# 03_I2S.net
KiCad netlist of a schematic drawn in Altium Designer
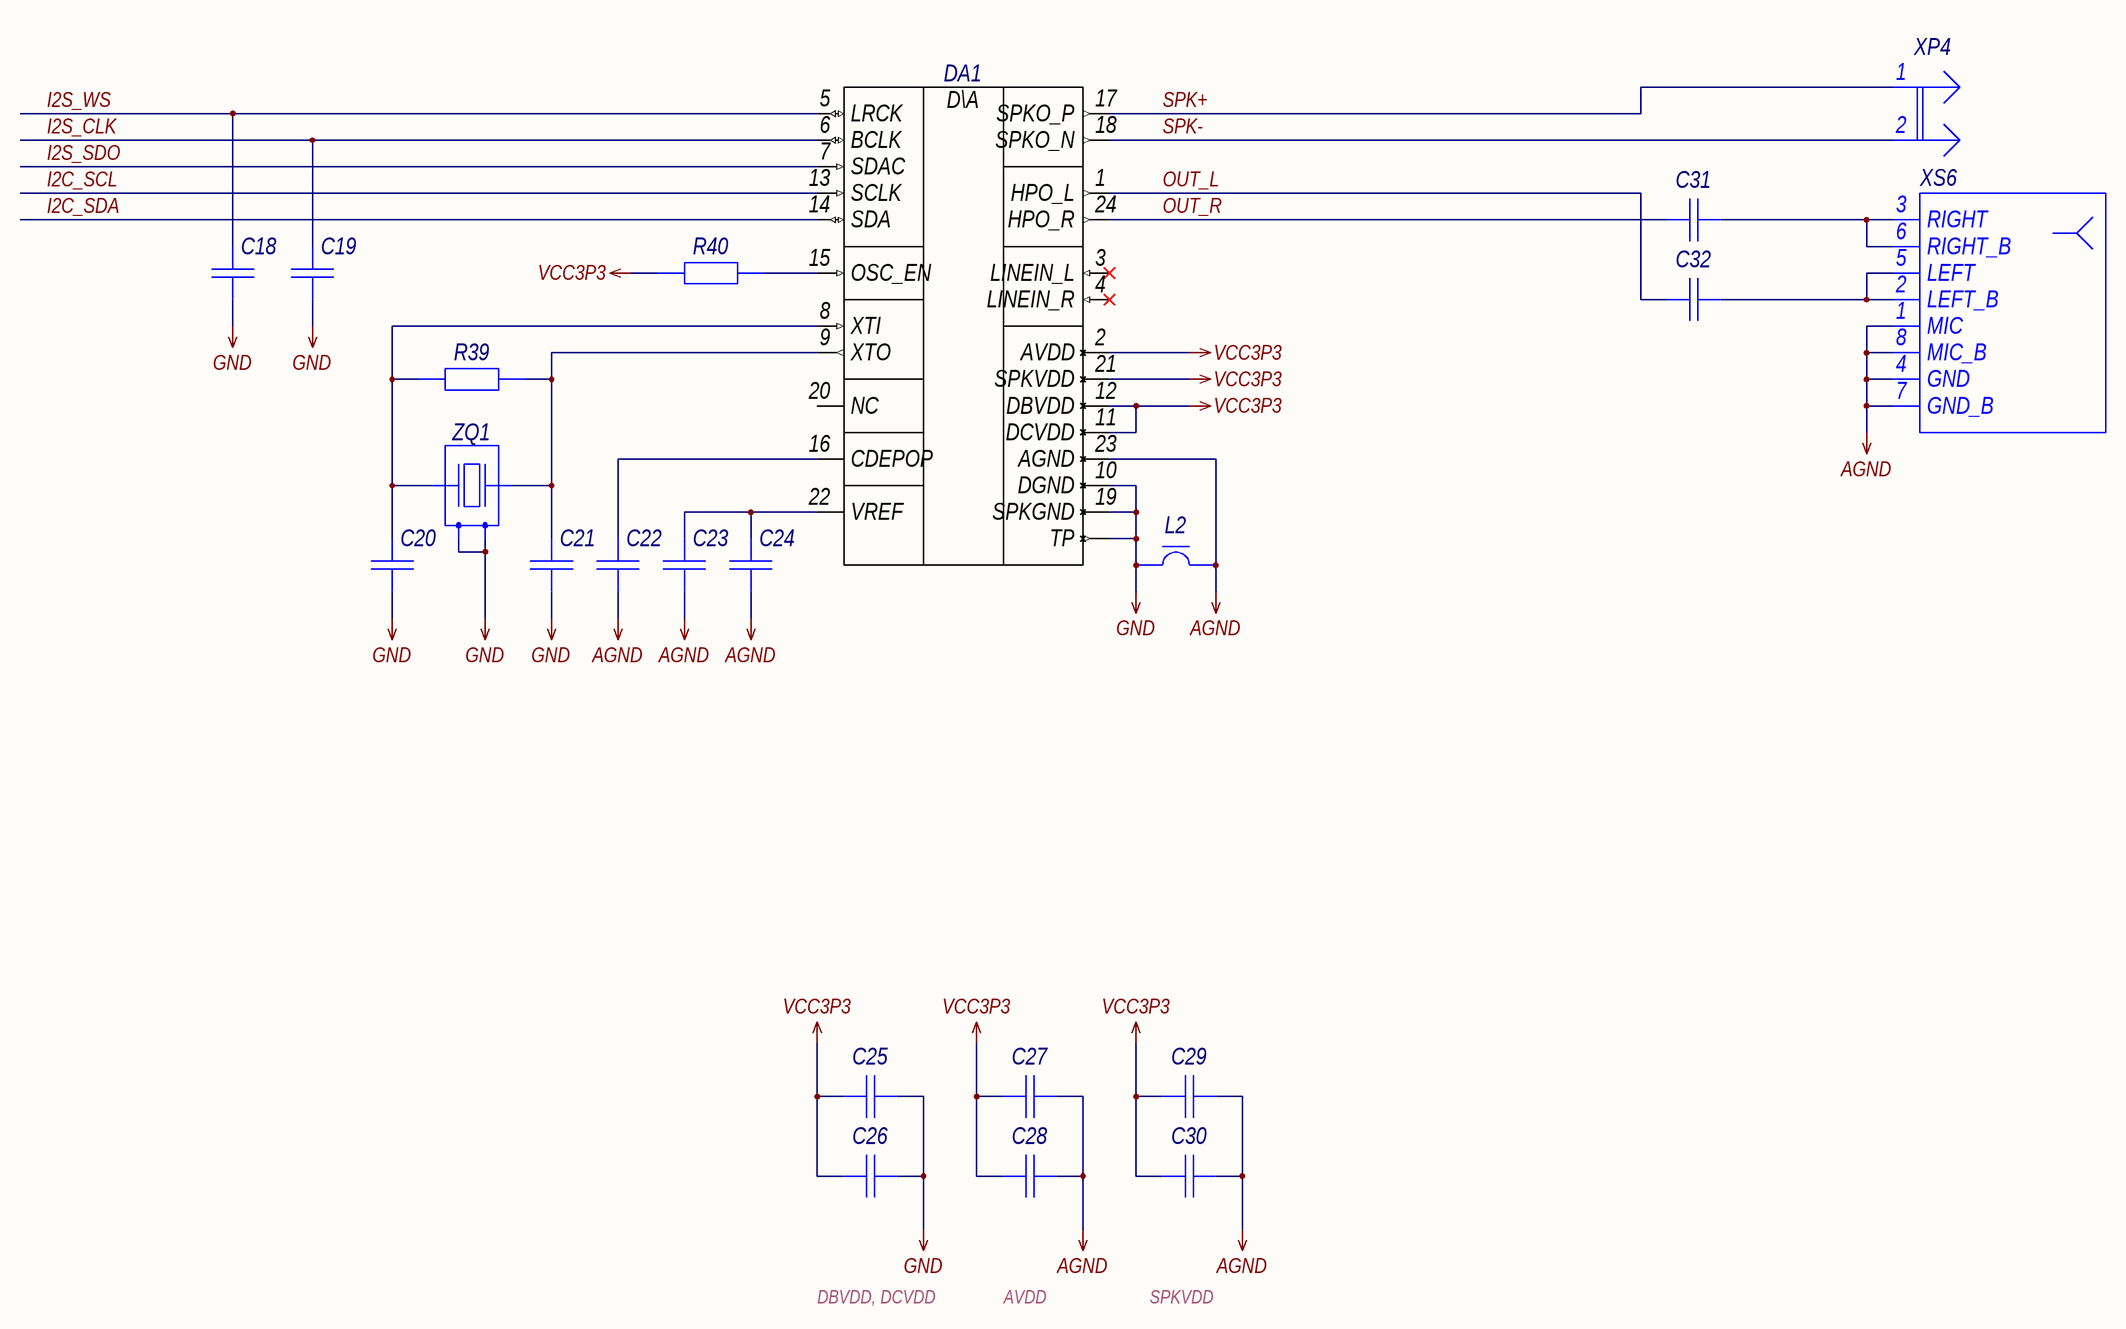
[diagram p0: 03_I2S.SchDoc]

(export (version "E")
  (design (tool "Eeschema 10.0.6"))
  (components
    (comp (ref "C18")
      (value "Capacitor")
      (footprint "C0603_L")
      (fields
        (field (name "PART NUMBER") "GRM1885C1H220JA01D")
        (field (name "VOLTAGE") "50V")
        (field (name "TOLERANCE") "±5%")
        (field (name "PUBLISHER") "Andrew Danich")
      )
      (libsource (lib "ADLib") (part "Capacitor"))
    )
    (comp (ref "C19")
      (value "Capacitor")
      (footprint "C0603_L")
      (fields
        (field (name "PART NUMBER") "GRM1885C1H220JA01D")
        (field (name "VOLTAGE") "50V")
        (field (name "TOLERANCE") "±5%")
        (field (name "PUBLISHER") "Andrew Danich")
      )
      (libsource (lib "ADLib") (part "Capacitor"))
    )
    (comp (ref "C20")
      (value "Capacitor")
      (footprint "C0603_L")
      (fields
        (field (name "PART NUMBER") "GCM1885C2A120JA16D")
        (field (name "VOLTAGE") "100V")
        (field (name "TOLERANCE") "±5%")
        (field (name "PUBLISHER") "Andrew Danich")
      )
      (libsource (lib "ADLib") (part "Capacitor"))
    )
    (comp (ref "C21")
      (value "Capacitor")
      (footprint "C0603_L")
      (fields
        (field (name "PART NUMBER") "GCM1885C2A120JA16D")
        (field (name "VOLTAGE") "100V")
        (field (name "TOLERANCE") "±5%")
        (field (name "PUBLISHER") "Andrew Danich")
      )
      (libsource (lib "ADLib") (part "Capacitor"))
    )
    (comp (ref "C22")
      (value "Capacitor")
      (footprint "C0603_L")
      (fields
        (field (name "PART NUMBER") "GCM188R71E105KA64D")
        (field (name "VOLTAGE") "25V")
        (field (name "TOLERANCE") "±10%")
        (field (name "PUBLISHER") "Andrew Danich")
      )
      (libsource (lib "ADLib") (part "Capacitor"))
    )
    (comp (ref "C23")
      (value "Capacitor")
      (footprint "C0603_L")
      (fields
        (field (name "PART NUMBER") "GRM188R72A104KA35D")
        (field (name "VOLTAGE") "100V")
        (field (name "TOLERANCE") "±10%")
        (field (name "PUBLISHER") "Andrew Danich")
      )
      (libsource (lib "ADLib") (part "Capacitor"))
    )
    (comp (ref "C24")
      (value "Capacitor")
      (footprint "C0603_L")
      (fields
        (field (name "PART NUMBER") "GRT188C81E475KE13D")
        (field (name "VOLTAGE") "25V")
        (field (name "TOLERANCE") "±20%")
        (field (name "PUBLISHER") "Andrew Danich")
      )
      (libsource (lib "ADLib") (part "Capacitor"))
    )
    (comp (ref "C25")
      (value "Capacitor")
      (footprint "C0603_L")
      (fields
        (field (name "PART NUMBER") "GCM188R71E105KA64D")
        (field (name "VOLTAGE") "25V")
        (field (name "TOLERANCE") "±10%")
        (field (name "PUBLISHER") "Andrew Danich")
      )
      (libsource (lib "ADLib") (part "Capacitor"))
    )
    (comp (ref "C26")
      (value "Capacitor")
      (footprint "C0603_L")
      (fields
        (field (name "PART NUMBER") "GRM1885C2A102JA01D")
        (field (name "VOLTAGE") "100V")
        (field (name "TOLERANCE") "±5%")
        (field (name "PUBLISHER") "Andrew Danich")
      )
      (libsource (lib "ADLib") (part "Capacitor"))
    )
    (comp (ref "C27")
      (value "Capacitor")
      (footprint "C0603_L")
      (fields
        (field (name "PART NUMBER") "GCM188R71E105KA64D")
        (field (name "VOLTAGE") "25V")
        (field (name "TOLERANCE") "±10%")
        (field (name "PUBLISHER") "Andrew Danich")
      )
      (libsource (lib "ADLib") (part "Capacitor"))
    )
    (comp (ref "C28")
      (value "Capacitor")
      (footprint "C0603_L")
      (fields
        (field (name "PART NUMBER") "GRM1885C2A102JA01D")
        (field (name "VOLTAGE") "100V")
        (field (name "TOLERANCE") "±5%")
        (field (name "PUBLISHER") "Andrew Danich")
      )
      (libsource (lib "ADLib") (part "Capacitor"))
    )
    (comp (ref "C29")
      (value "Capacitor")
      (footprint "C0603_L")
      (fields
        (field (name "PART NUMBER") "GRM188R61A106KE69D")
        (field (name "VOLTAGE") "10V")
        (field (name "TOLERANCE") "±10%")
        (field (name "PUBLISHER") "Andrew Danich")
      )
      (libsource (lib "ADLib") (part "Capacitor"))
    )
    (comp (ref "C30")
      (value "Capacitor")
      (footprint "C0603_L")
      (fields
        (field (name "PART NUMBER") "GRM1885C2A102JA01D")
        (field (name "VOLTAGE") "100V")
        (field (name "TOLERANCE") "±5%")
        (field (name "PUBLISHER") "Andrew Danich")
      )
      (libsource (lib "ADLib") (part "Capacitor"))
    )
    (comp (ref "C31")
      (value "Capacitor")
      (footprint "C1210_L")
      (fields
        (field (name "PART NUMBER") "GRM32ER60J107ME20L")
        (field (name "VOLTAGE") "6.3V")
        (field (name "TOLERANCE") "±20%")
        (field (name "PUBLISHER") "Andrew Danich")
      )
      (libsource (lib "ADLib") (part "Capacitor"))
    )
    (comp (ref "C32")
      (value "Capacitor")
      (footprint "C1210_L")
      (fields
        (field (name "PART NUMBER") "GRM32ER60J107ME20L")
        (field (name "VOLTAGE") "6.3V")
        (field (name "TOLERANCE") "±20%")
        (field (name "PUBLISHER") "Andrew Danich")
      )
      (libsource (lib "ADLib") (part "Capacitor"))
    )
    (comp (ref "DA1")
      (value "ALC5628")
      (footprint "QFN-24_050P400X400X090_N")
      (fields
        (field (name "PART NUMBER") "ALC5628-GR")
        (field (name "MANUFACTURER") "Realtek")
        (field (name "PUBLISHER") "Andrew Danich")
      )
      (libsource (lib "ADLib") (part "ALC5628"))
    )
    (comp (ref "L2")
      (value "FerriteBead")
      (footprint "L0603_L")
      (fields
        (field (name "PART NUMBER") "BLM18PG121SN1")
        (field (name "MANUFACTURER") "Murata")
        (field (name "PUBLISHER") "Andrew Danich")
      )
      (libsource (lib "ADLib") (part "FerriteBead"))
    )
    (comp (ref "R39")
      (value "Resistor")
      (footprint "R0603_L")
      (fields
        (field (name "PART NUMBER") "RC0603JR-071ML")
        (field (name "TOLERANCE") "±5%")
        (field (name "MANUFACTURER") "Yageo")
        (field (name "PUBLISHER") "Andrew Danich")
      )
      (libsource (lib "ADLib") (part "Resistor"))
    )
    (comp (ref "R40")
      (value "Resistor")
      (footprint "R0603_L")
      (fields
        (field (name "PART NUMBER") "RC0603JR-070R")
        (field (name "TOLERANCE") "±5%")
        (field (name "MANUFACTURER") "Yageo")
        (field (name "PUBLISHER") "Andrew Danich")
      )
      (libsource (lib "ADLib") (part "Resistor"))
    )
    (comp (ref "XP4")
      (value "SPK")
      (footprint "MW-2M")
      (fields (field (name "PART NUMBER") "MW-2M") (field (name "PUBLISHER") "Andrew Danich"))
      (libsource (lib "ADLib") (part "Con-2-M"))
    )
    (comp (ref "XS6")
      (value "OUT")
      (footprint "PJ30930-Series")
      (fields
        (field (name "PART NUMBER") "PJ30930-Q-LC0AG00TR-7260")
        (field (name "MANUFACTURER") "Dongnan Electronics")
        (field (name "PUBLISHER") "Andrew Danich")
      )
      (libsource (lib "ADLib") (part "PJ30930-Q-LCxx00x-7260"))
    )
    (comp (ref "ZQ1")
      (value "Crystal-1_3p_S")
      (footprint "SMD 3.2x2.5mm")
      (fields
        (field (name "PART NUMBER") "MCSJK-7U-24.576-12-30-60-B-30")
        (field (name "MANUFACTURER") "Multicomp")
        (field (name "PUBLISHER") "Andrew Danich")
      )
      (libsource (lib "ADLib") (part "Crystal-1_3p_S"))
    )
  )
  (nets
    (net (code "1") (name "/I2C_SCL") (class "Default")
      (node (ref "DA1") (pin "13") (pinfunction "SCLK_13") (pintype "input"))
    )
    (net (code "2") (name "/I2C_SDA") (class "Default")
      (node (ref "DA1") (pin "14") (pinfunction "SDA_14") (pintype "bidirectional"))
    )
    (net (code "3") (name "/I2S_CLK") (class "Default")
      (node (ref "C19") (pin "2") (pinfunction "2_2") (pintype "passive"))
      (node (ref "DA1") (pin "6") (pinfunction "BCLK_6") (pintype "bidirectional"))
    )
    (net (code "4") (name "/I2S_SDO") (class "Default")
      (node (ref "DA1") (pin "7") (pinfunction "SDAC_7") (pintype "input"))
    )
    (net (code "5") (name "/I2S_WS") (class "Default")
      (node (ref "C18") (pin "2") (pinfunction "2_2") (pintype "passive"))
      (node (ref "DA1") (pin "5") (pinfunction "LRCK_5") (pintype "bidirectional"))
    )
    (net (code "6") (name "/OUT_L") (class "Default")
      (node (ref "C32") (pin "1") (pinfunction "1_1") (pintype "passive"))
      (node (ref "DA1") (pin "1") (pinfunction "HPO_L_1") (pintype "output"))
    )
    (net (code "7") (name "/OUT_R") (class "Default")
      (node (ref "C31") (pin "1") (pinfunction "1_1") (pintype "passive"))
      (node (ref "DA1") (pin "24") (pinfunction "HPO_R_24") (pintype "output"))
    )
    (net (code "8") (name "/SPK+") (class "Default")
      (node (ref "DA1") (pin "17") (pinfunction "SPKO_P_17") (pintype "output"))
      (node (ref "XP4") (pin "1") (pintype "passive"))
    )
    (net (code "9") (name "/SPK-") (class "Default")
      (node (ref "DA1") (pin "18") (pinfunction "SPKO_N_18") (pintype "output"))
      (node (ref "XP4") (pin "2") (pintype "passive"))
    )
    (net (code "10") (name "AGND") (class "Default")
      (node (ref "C22") (pin "1") (pinfunction "1_1") (pintype "passive"))
      (node (ref "C23") (pin "1") (pinfunction "1_1") (pintype "passive"))
      (node (ref "C24") (pin "1") (pinfunction "1_1") (pintype "passive"))
      (node (ref "C27") (pin "2") (pinfunction "2_2") (pintype "passive"))
      (node (ref "C28") (pin "2") (pinfunction "2_2") (pintype "passive"))
      (node (ref "C29") (pin "2") (pinfunction "2_2") (pintype "passive"))
      (node (ref "C30") (pin "2") (pinfunction "2_2") (pintype "passive"))
      (node (ref "DA1") (pin "23") (pinfunction "AGND_23") (pintype "power_in"))
      (node (ref "L2") (pin "2") (pinfunction "2_2") (pintype "passive"))
      (node (ref "XS6") (pin "1") (pinfunction "MIC_1") (pintype "passive"))
      (node (ref "XS6") (pin "4") (pinfunction "GND_4") (pintype "passive"))
      (node (ref "XS6") (pin "7") (pinfunction "GND_B_7") (pintype "passive"))
      (node (ref "XS6") (pin "8") (pinfunction "MIC_B_8") (pintype "passive"))
    )
    (net (code "11") (name "GND") (class "Default")
      (node (ref "C18") (pin "1") (pinfunction "1_1") (pintype "passive"))
      (node (ref "C19") (pin "1") (pinfunction "1_1") (pintype "passive"))
      (node (ref "C20") (pin "1") (pinfunction "1_1") (pintype "passive"))
      (node (ref "C21") (pin "1") (pinfunction "1_1") (pintype "passive"))
      (node (ref "C25") (pin "2") (pinfunction "2_2") (pintype "passive"))
      (node (ref "C26") (pin "2") (pinfunction "2_2") (pintype "passive"))
      (node (ref "DA1") (pin "10") (pinfunction "DGND_10") (pintype "power_in"))
      (node (ref "DA1") (pin "19") (pinfunction "SPKGND_19") (pintype "power_in"))
      (node (ref "DA1") (pin "TP") (pinfunction "TP_TP") (pintype "output"))
      (node (ref "L2") (pin "1") (pinfunction "1_1") (pintype "passive"))
      (node (ref "ZQ1") (pin "2") (pinfunction "2_2") (pintype "passive"))
      (node (ref "ZQ1") (pin "4") (pinfunction "4_4") (pintype "passive"))
    )
    (net (code "12") (name "Net-(DA1-CDEPOP)") (class "Default")
      (node (ref "C22") (pin "2") (pinfunction "2_2") (pintype "passive"))
      (node (ref "DA1") (pin "16") (pinfunction "CDEPOP_16") (pintype "passive"))
    )
    (net (code "13") (name "Net-(DA1-OSC_EN)") (class "Default")
      (node (ref "DA1") (pin "15") (pinfunction "OSC_EN_15") (pintype "input"))
      (node (ref "R40") (pin "2") (pinfunction "2_2") (pintype "passive"))
    )
    (net (code "14") (name "Net-(DA1-VREF)") (class "Default")
      (node (ref "C23") (pin "2") (pinfunction "2_2") (pintype "passive"))
      (node (ref "C24") (pin "2") (pinfunction "2_2") (pintype "passive"))
      (node (ref "DA1") (pin "22") (pinfunction "VREF_22") (pintype "passive"))
    )
    (net (code "15") (name "Net-(DA1-XTI)") (class "Default")
      (node (ref "C20") (pin "2") (pinfunction "2_2") (pintype "passive"))
      (node (ref "DA1") (pin "8") (pinfunction "XTI_8") (pintype "input"))
      (node (ref "R39") (pin "1") (pinfunction "1_1") (pintype "passive"))
      (node (ref "ZQ1") (pin "1") (pinfunction "1_1") (pintype "passive"))
    )
    (net (code "16") (name "Net-(DA1-XTO)") (class "Default")
      (node (ref "C21") (pin "2") (pinfunction "2_2") (pintype "passive"))
      (node (ref "DA1") (pin "9") (pinfunction "XTO_9") (pintype "output"))
      (node (ref "R39") (pin "2") (pinfunction "2_2") (pintype "passive"))
      (node (ref "ZQ1") (pin "3") (pinfunction "3_3") (pintype "passive"))
    )
    (net (code "17") (name "Net-(XS6-LEFT)") (class "Default")
      (node (ref "C32") (pin "2") (pinfunction "2_2") (pintype "passive"))
      (node (ref "XS6") (pin "2") (pinfunction "LEFT_B_2") (pintype "passive"))
      (node (ref "XS6") (pin "5") (pinfunction "LEFT_5") (pintype "passive"))
    )
    (net (code "18") (name "Net-(XS6-RIGHT)") (class "Default")
      (node (ref "C31") (pin "2") (pinfunction "2_2") (pintype "passive"))
      (node (ref "XS6") (pin "3") (pinfunction "RIGHT_3") (pintype "passive"))
      (node (ref "XS6") (pin "6") (pinfunction "RIGHT_B_6") (pintype "passive"))
    )
    (net (code "19") (name "VCC3P3") (class "Default")
      (node (ref "C25") (pin "1") (pinfunction "1_1") (pintype "passive"))
      (node (ref "C26") (pin "1") (pinfunction "1_1") (pintype "passive"))
      (node (ref "C27") (pin "1") (pinfunction "1_1") (pintype "passive"))
      (node (ref "C28") (pin "1") (pinfunction "1_1") (pintype "passive"))
      (node (ref "C29") (pin "1") (pinfunction "1_1") (pintype "passive"))
      (node (ref "C30") (pin "1") (pinfunction "1_1") (pintype "passive"))
      (node (ref "DA1") (pin "11") (pinfunction "DCVDD_11") (pintype "power_in"))
      (node (ref "DA1") (pin "12") (pinfunction "DBVDD_12") (pintype "power_in"))
      (node (ref "DA1") (pin "2") (pinfunction "AVDD_2") (pintype "power_in"))
      (node (ref "DA1") (pin "21") (pinfunction "SPKVDD_21") (pintype "power_in"))
      (node (ref "R40") (pin "1") (pinfunction "1_1") (pintype "passive"))
    )
    (net (code "20") (name "unconnected-(DA1-LINEIN_L-Pad3)") (class "Default")
      (node (ref "DA1") (pin "3") (pinfunction "LINEIN_L_3") (pintype "input+no_connect"))
    )
    (net (code "21") (name "unconnected-(DA1-LINEIN_R-Pad4)") (class "Default")
      (node (ref "DA1") (pin "4") (pinfunction "LINEIN_R_4") (pintype "input+no_connect"))
    )
    (net (code "22") (name "unconnected-(DA1-NC-Pad20)") (class "Default")
      (node (ref "DA1") (pin "20") (pinfunction "NC_20") (pintype "passive"))
    )
  )
)
